# powerAmp.net
KiCad netlist of a schematic drawn in Altium Designer
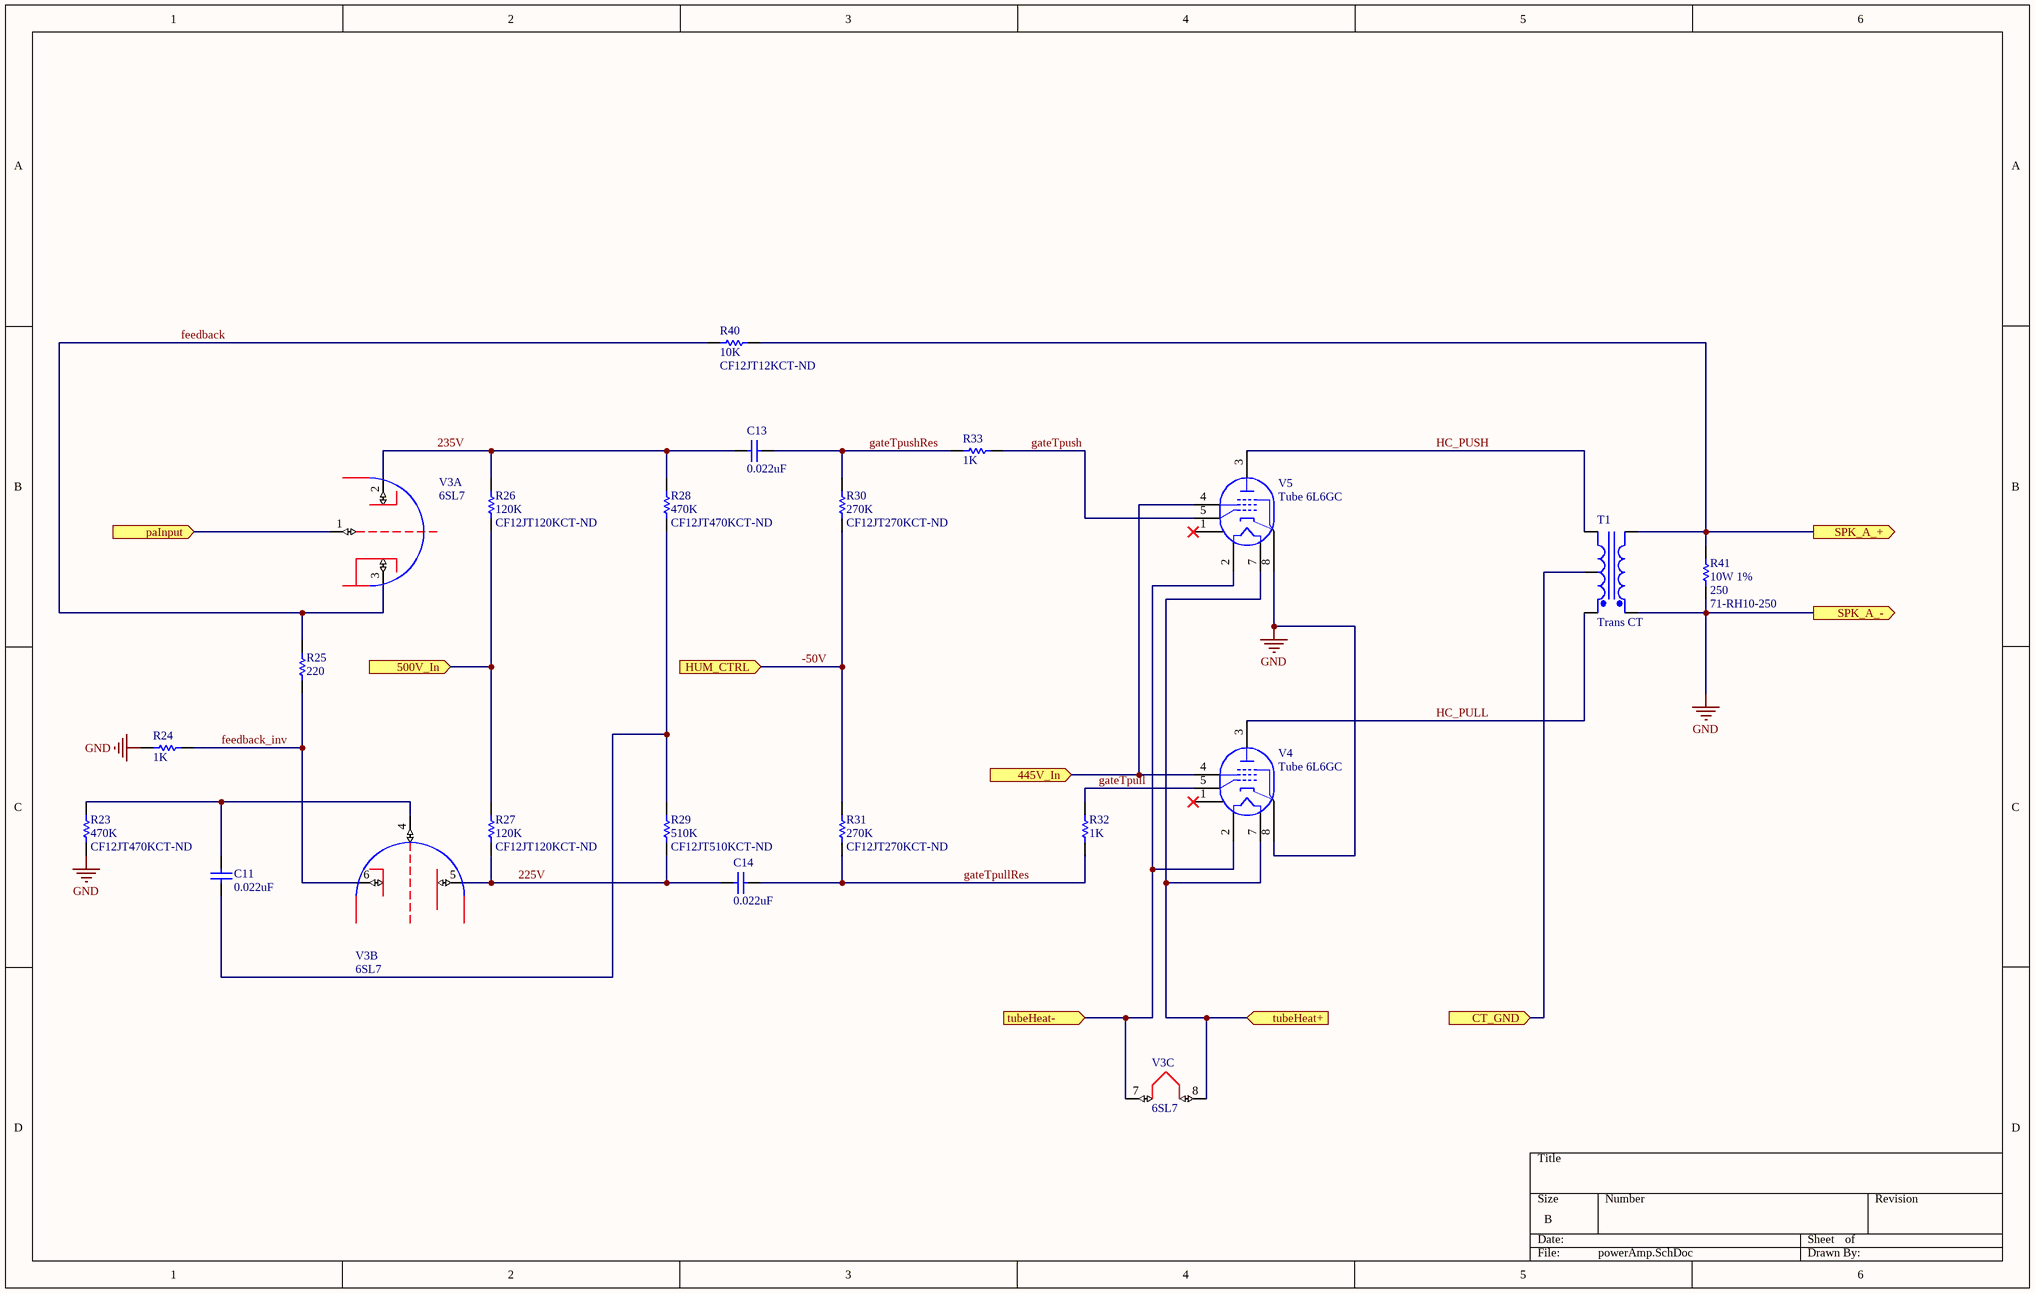
[diagram p0: powerAmp.SchDoc]

(export (version "E")
  (design (tool "Eeschema 10.0.6"))
  (components
    (comp (ref "C11")
      (value "0.022uF")
      (footprint "RAD-0.3")
      (description "Capacitor")
      (fields (field (name "Comment") "Cap") (field (name "PUBLISHER") "Altium Limited"))
      (libsource (lib "Miscellaneous Devices") (part "Cap"))
    )
    (comp (ref "C13")
      (value "0.022uF")
      (footprint "RAD-0.3")
      (description "Capacitor")
      (fields (field (name "Comment") "Cap") (field (name "PUBLISHER") "Altium Limited"))
      (libsource (lib "Miscellaneous Devices") (part "Cap"))
    )
    (comp (ref "C14")
      (value "0.022uF")
      (footprint "RAD-0.3")
      (description "Capacitor")
      (fields (field (name "Comment") "Cap") (field (name "PUBLISHER") "Altium Limited"))
      (libsource (lib "Miscellaneous Devices") (part "Cap"))
    )
    (comp (ref "R23")
      (value "470K")
      (footprint "AXIAL-0.3")
      (description "Resistor")
      (fields
        (field (name "SUPPLIER PART NUMBER 1") "CF12JT470KCT-ND")
        (field (name "Comment") "Res1")
        (field (name "PUBLISHER") "Altium Limited")
      )
      (libsource (lib "Miscellaneous Devices") (part "Res1"))
    )
    (comp (ref "R24")
      (value "1K")
      (footprint "AXIAL-0.3")
      (description "Resistor")
      (fields (field (name "Comment") "Res1") (field (name "PUBLISHER") "Altium Limited"))
      (libsource (lib "Miscellaneous Devices") (part "Res1"))
    )
    (comp (ref "R25")
      (value "220")
      (footprint "AXIAL-0.3")
      (description "Resistor")
      (fields (field (name "Comment") "Res1") (field (name "PUBLISHER") "Altium Limited"))
      (libsource (lib "Miscellaneous Devices") (part "Res1"))
    )
    (comp (ref "R26")
      (value "120K")
      (footprint "AXIAL-0.3")
      (description "Resistor")
      (fields
        (field (name "SUPPLIER PART NUMBER 1") "CF12JT120KCT-ND")
        (field (name "Comment") "Res1")
        (field (name "PUBLISHER") "Altium Limited")
      )
      (libsource (lib "Miscellaneous Devices") (part "Res1"))
    )
    (comp (ref "R27")
      (value "120K")
      (footprint "AXIAL-0.3")
      (description "Resistor")
      (fields
        (field (name "SUPPLIER PART NUMBER 1") "CF12JT120KCT-ND")
        (field (name "Comment") "Res1")
        (field (name "PUBLISHER") "Altium Limited")
      )
      (libsource (lib "Miscellaneous Devices") (part "Res1"))
    )
    (comp (ref "R28")
      (value "470K")
      (footprint "AXIAL-0.3")
      (description "Resistor")
      (fields
        (field (name "SUPPLIER PART NUMBER 1") "CF12JT470KCT-ND")
        (field (name "Comment") "Res1")
        (field (name "PUBLISHER") "Altium Limited")
      )
      (libsource (lib "Miscellaneous Devices") (part "Res1"))
    )
    (comp (ref "R29")
      (value "510K")
      (footprint "AXIAL-0.3")
      (description "Resistor")
      (fields
        (field (name "SUPPLIER PART NUMBER 1") "CF12JT510KCT-ND")
        (field (name "Comment") "Res1")
        (field (name "PUBLISHER") "Altium Limited")
      )
      (libsource (lib "Miscellaneous Devices") (part "Res1"))
    )
    (comp (ref "R30")
      (value "270K")
      (footprint "AXIAL-0.3")
      (description "Resistor")
      (fields
        (field (name "SUPPLIER PART NUMBER 1") "CF12JT270KCT-ND")
        (field (name "Comment") "Res1")
        (field (name "PUBLISHER") "Altium Limited")
      )
      (libsource (lib "Miscellaneous Devices") (part "Res1"))
    )
    (comp (ref "R31")
      (value "270K")
      (footprint "AXIAL-0.3")
      (description "Resistor")
      (fields
        (field (name "SUPPLIER PART NUMBER 1") "CF12JT270KCT-ND")
        (field (name "Comment") "Res1")
        (field (name "PUBLISHER") "Altium Limited")
      )
      (libsource (lib "Miscellaneous Devices") (part "Res1"))
    )
    (comp (ref "R32")
      (value "1K")
      (footprint "AXIAL-0.3")
      (description "Resistor")
      (fields (field (name "Comment") "Res1") (field (name "PUBLISHER") "Altium Limited"))
      (libsource (lib "Miscellaneous Devices") (part "Res1"))
    )
    (comp (ref "R33")
      (value "1K")
      (footprint "AXIAL-0.3")
      (description "Resistor")
      (fields (field (name "Comment") "Res1") (field (name "PUBLISHER") "Altium Limited"))
      (libsource (lib "Miscellaneous Devices") (part "Res1"))
    )
    (comp (ref "R40")
      (value "10K")
      (footprint "AXIAL-0.3")
      (description "Resistor")
      (fields
        (field (name "SUPPLIER PART NUMBER 1") "CF12JT12KCT-ND")
        (field (name "Comment") "Res1")
        (field (name "PUBLISHER") "Altium Limited")
      )
      (libsource (lib "Miscellaneous Devices") (part "Res1"))
    )
    (comp (ref "R41")
      (value "10W 1%")
      (footprint "AXIAL-0.3")
      (description "Resistor")
      (fields
        (field (name "ALTIUM_VALUE") "250")
        (field (name "SUPPLIER PART NUMBER 1") "71-RH10-250")
        (field (name "PUBLISHER") "Altium Limited")
      )
      (libsource (lib "Miscellaneous Devices") (part "Res1"))
    )
    (comp (ref "T1")
      (value "Trans CT")
      (footprint "HDR1X5")
      (description "Center-Tapped Transformer (Coupled Inductor Model)")
      (fields (field (name "PUBLISHER") "Altium Limited"))
      (libsource (lib "Miscellaneous Devices") (part "Trans CT"))
    )
    (comp (ref "V3") (value "6SL7") (footprint "OCTALSOCKET") (libsource (lib "amp_lib") (part "6SL7")))
    (comp (ref "V4")
      (value "Tube 6L6GC")
      (footprint "OCTALSOCKET")
      (description "Beam Power Pentode")
      (fields (field (name "PUBLISHER") "Altium Limited"))
      (libsource (lib "Miscellaneous Devices") (part "Tube 6L6GC"))
    )
    (comp (ref "V5")
      (value "Tube 6L6GC")
      (footprint "OCTALSOCKET")
      (description "Beam Power Pentode")
      (fields (field (name "PUBLISHER") "Altium Limited"))
      (libsource (lib "Miscellaneous Devices") (part "Tube 6L6GC"))
    )
  )
  (nets
    (net (code "1") (name "/-50V") (class "Default")
      (node (ref "R30") (pin "1") (pinfunction "1_1") (pintype "passive"))
      (node (ref "R31") (pin "2") (pinfunction "2_2") (pintype "passive"))
    )
    (net (code "2") (name "/225V") (class "Default")
      (node (ref "C14") (pin "1") (pinfunction "1_1") (pintype "passive"))
      (node (ref "R27") (pin "1") (pinfunction "1_1") (pintype "passive"))
      (node (ref "R29") (pin "2") (pinfunction "2_2") (pintype "passive"))
      (node (ref "V3") (pin "5") (pinfunction "topPlate_5") (pintype "bidirectional"))
    )
    (net (code "3") (name "/235V") (class "Default")
      (node (ref "C13") (pin "1") (pinfunction "1_1") (pintype "passive"))
      (node (ref "R26") (pin "2") (pinfunction "2_2") (pintype "passive"))
      (node (ref "R28") (pin "1") (pinfunction "1_1") (pintype "passive"))
      (node (ref "V3") (pin "2") (pinfunction "topPlate_2") (pintype "bidirectional"))
    )
    (net (code "4") (name "/445V_In") (class "Default")
      (node (ref "V4") (pin "4") (pinfunction "GT2_4") (pintype "passive"))
      (node (ref "V5") (pin "4") (pinfunction "GT2_4") (pintype "passive"))
    )
    (net (code "5") (name "/500V_In") (class "Default")
      (node (ref "R26") (pin "1") (pinfunction "1_1") (pintype "passive"))
      (node (ref "R27") (pin "2") (pinfunction "2_2") (pintype "passive"))
    )
    (net (code "6") (name "/CT_GND") (class "Default")
      (node (ref "T1") (pin "4") (pinfunction "SecCT_4") (pintype "passive"))
    )
    (net (code "7") (name "/HC_PULL") (class "Default")
      (node (ref "T1") (pin "3") (pinfunction "Sec+_3") (pintype "passive"))
      (node (ref "V4") (pin "3") (pinfunction "PT_3") (pintype "passive"))
    )
    (net (code "8") (name "/HC_PUSH") (class "Default")
      (node (ref "T1") (pin "5") (pinfunction "Sec-_5") (pintype "passive"))
      (node (ref "V5") (pin "3") (pinfunction "PT_3") (pintype "passive"))
    )
    (net (code "9") (name "/SPK_A_+") (class "Default")
      (node (ref "R40") (pin "1") (pinfunction "1_1") (pintype "passive"))
      (node (ref "R41") (pin "2") (pinfunction "2_2") (pintype "passive"))
      (node (ref "T1") (pin "2") (pinfunction "Pri-_2") (pintype "passive"))
    )
    (net (code "10") (name "/feedback") (class "Default")
      (node (ref "R25") (pin "2") (pinfunction "2_2") (pintype "passive"))
      (node (ref "R40") (pin "2") (pinfunction "2_2") (pintype "passive"))
      (node (ref "V3") (pin "3") (pinfunction "topPlate_3") (pintype "bidirectional"))
    )
    (net (code "11") (name "/feedback_inv") (class "Default")
      (node (ref "R24") (pin "1") (pinfunction "1_1") (pintype "passive"))
      (node (ref "R25") (pin "1") (pinfunction "1_1") (pintype "passive"))
      (node (ref "V3") (pin "6") (pinfunction "topPlate_6") (pintype "bidirectional"))
    )
    (net (code "12") (name "/gateTpull") (class "Default")
      (node (ref "R32") (pin "1") (pinfunction "1_1") (pintype "passive"))
      (node (ref "V4") (pin "5") (pinfunction "GT1_5") (pintype "passive"))
    )
    (net (code "13") (name "/gateTpullRes") (class "Default")
      (node (ref "C14") (pin "2") (pinfunction "2_2") (pintype "passive"))
      (node (ref "R31") (pin "1") (pinfunction "1_1") (pintype "passive"))
      (node (ref "R32") (pin "2") (pinfunction "2_2") (pintype "passive"))
    )
    (net (code "14") (name "/gateTpush") (class "Default")
      (node (ref "R33") (pin "1") (pinfunction "1_1") (pintype "passive"))
      (node (ref "V5") (pin "5") (pinfunction "GT1_5") (pintype "passive"))
    )
    (net (code "15") (name "/gateTpushRes") (class "Default")
      (node (ref "C13") (pin "2") (pinfunction "2_2") (pintype "passive"))
      (node (ref "R30") (pin "2") (pinfunction "2_2") (pintype "passive"))
      (node (ref "R33") (pin "2") (pinfunction "2_2") (pintype "passive"))
    )
    (net (code "16") (name "/paInput") (class "Default")
      (node (ref "V3") (pin "1") (pinfunction "gate_1") (pintype "bidirectional"))
    )
    (net (code "17") (name "/tubeHeat+") (class "Default")
      (node (ref "V3") (pin "8") (pinfunction "8_8") (pintype "bidirectional"))
      (node (ref "V4") (pin "7") (pinfunction "H_7") (pintype "passive"))
      (node (ref "V5") (pin "7") (pinfunction "H_7") (pintype "passive"))
    )
    (net (code "18") (name "/tubeHeat-") (class "Default")
      (node (ref "V3") (pin "7") (pinfunction "7_7") (pintype "bidirectional"))
      (node (ref "V4") (pin "2") (pinfunction "H_2") (pintype "passive"))
      (node (ref "V5") (pin "2") (pinfunction "H_2") (pintype "passive"))
    )
    (net (code "19") (name "GND") (class "Default")
      (node (ref "R23") (pin "2") (pinfunction "2_2") (pintype "passive"))
      (node (ref "R24") (pin "2") (pinfunction "2_2") (pintype "passive"))
      (node (ref "R41") (pin "1") (pinfunction "1_1") (pintype "passive"))
      (node (ref "T1") (pin "1") (pinfunction "Pri+_1") (pintype "passive"))
      (node (ref "V4") (pin "8") (pinfunction "G3,_KT_8") (pintype "passive"))
      (node (ref "V5") (pin "8") (pinfunction "G3,_KT_8") (pintype "passive"))
    )
    (net (code "20") (name "Net-(C11-Pad1)") (class "Default")
      (node (ref "C11") (pin "1") (pinfunction "1_1") (pintype "passive"))
      (node (ref "R28") (pin "2") (pinfunction "2_2") (pintype "passive"))
      (node (ref "R29") (pin "1") (pinfunction "1_1") (pintype "passive"))
    )
    (net (code "21") (name "Net-(V3B-gate)") (class "Default")
      (node (ref "C11") (pin "2") (pinfunction "2_2") (pintype "passive"))
      (node (ref "R23") (pin "1") (pinfunction "1_1") (pintype "passive"))
      (node (ref "V3") (pin "4") (pinfunction "gate_4") (pintype "bidirectional"))
    )
    (net (code "22") (name "unconnected-(V4-NC-Pad1)") (class "Default")
      (node (ref "V4") (pin "1") (pinfunction "NC_1") (pintype "passive+no_connect"))
    )
    (net (code "23") (name "unconnected-(V5-NC-Pad1)") (class "Default")
      (node (ref "V5") (pin "1") (pinfunction "NC_1") (pintype "passive+no_connect"))
    )
  )
)
